# Ultrassom_Breakout_-_V1.net
KiCad netlist of a schematic drawn in EAGLE
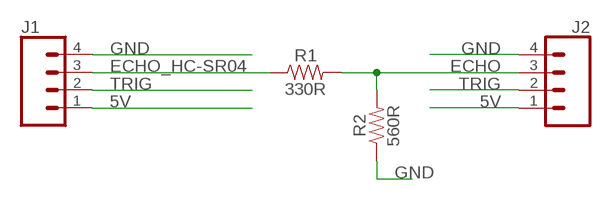
[diagram p0: schematic, sheet 1]

(export (version "E")
  (design (tool "Eeschema 10.0.6"))
  (components
    (comp (ref "J1")
      (value "CONN_041X04_NO_SILK")
      (footprint "eagle-import:1X04_NO_SILK")
      (libsource (lib "eagle-import") (part "CONN_041X04_NO_SILK"))
    )
    (comp (ref "J2")
      (value "CONN_041X04_NO_SILK")
      (footprint "eagle-import:1X04_NO_SILK")
      (libsource (lib "eagle-import") (part "CONN_041X04_NO_SILK"))
    )
    (comp (ref "R1")
      (value "330R")
      (footprint "eagle-import:AXIAL-0.3-KIT")
      (libsource (lib "eagle-import") (part "RESISTORAXIAL-0.3-KIT"))
    )
    (comp (ref "R2")
      (value "560R")
      (footprint "eagle-import:AXIAL-0.3-KIT")
      (libsource (lib "eagle-import") (part "RESISTORAXIAL-0.3-KIT"))
    )
  )
  (nets
    (net (code "1") (name "5V") (class "Default")
      (node (ref "J1") (pin "1") (pinfunction "1_1") (pintype "passive"))
      (node (ref "J2") (pin "1") (pinfunction "1_1") (pintype "passive"))
    )
    (net (code "2") (name "ECHO") (class "Default")
      (node (ref "J2") (pin "3") (pinfunction "3_3") (pintype "passive"))
      (node (ref "R1") (pin "P$2") (pinfunction "2_P$2") (pintype "passive"))
      (node (ref "R2") (pin "P$2") (pinfunction "2_P$2") (pintype "passive"))
    )
    (net (code "3") (name "ECHO_HC-SR04") (class "Default")
      (node (ref "J1") (pin "3") (pinfunction "3_3") (pintype "passive"))
      (node (ref "R1") (pin "P$1") (pinfunction "1_P$1") (pintype "passive"))
    )
    (net (code "4") (name "GND") (class "Default")
      (node (ref "J1") (pin "4") (pinfunction "4_4") (pintype "passive"))
      (node (ref "J2") (pin "4") (pinfunction "4_4") (pintype "passive"))
      (node (ref "R2") (pin "P$1") (pinfunction "1_P$1") (pintype "passive"))
    )
    (net (code "5") (name "TRIG") (class "Default")
      (node (ref "J1") (pin "2") (pinfunction "2_2") (pintype "passive"))
      (node (ref "J2") (pin "2") (pinfunction "2_2") (pintype "passive"))
    )
  )
)
